# compare2_1.net
KiCad netlist of a schematic drawn in EAGLE
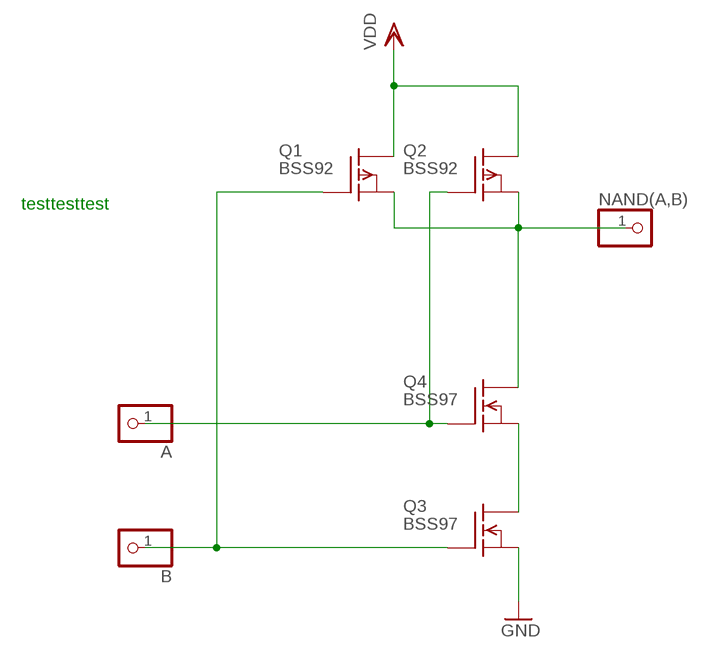
[diagram p0: schematic, sheet 1]

(export (version "E")
  (design (tool "Eeschema 10.0.6"))
  (components
    (comp (ref "A")
      (value "PINHD-1X1")
      (footprint "eagle-import:1X01")
      (libsource (lib "eagle-import") (part "PINHD-1X1"))
    )
    (comp (ref "B")
      (value "PINHD-1X1")
      (footprint "eagle-import:1X01")
      (libsource (lib "eagle-import") (part "PINHD-1X1"))
    )
    (comp (ref "NAND(A,B)")
      (value "PINHD-1X1")
      (footprint "eagle-import:1X01")
      (libsource (lib "eagle-import") (part "PINHD-1X1"))
    )
    (comp (ref "Q1")
      (value "BSS92")
      (footprint "eagle-import:TO92")
      (libsource (lib "eagle-import") (part "BSS92"))
    )
    (comp (ref "Q2")
      (value "BSS92")
      (footprint "eagle-import:TO92")
      (libsource (lib "eagle-import") (part "BSS92"))
    )
    (comp (ref "Q3")
      (value "BSS97")
      (footprint "eagle-import:TO202")
      (libsource (lib "eagle-import") (part "BSS97"))
    )
    (comp (ref "Q4")
      (value "BSS97")
      (footprint "eagle-import:TO202")
      (libsource (lib "eagle-import") (part "BSS97"))
    )
  )
  (nets
    (net (code "1") (name "GND") (class "Default")
      (node (ref "Q3") (pin "1") (pinfunction "S_1") (pintype "passive"))
    )
    (net (code "2") (name "Net-(Q1-G)") (class "Default")
      (node (ref "B") (pin "1") (pinfunction "1_1") (pintype "passive"))
      (node (ref "Q1") (pin "1") (pinfunction "G_1") (pintype "passive"))
      (node (ref "Q3") (pin "3") (pinfunction "G_3") (pintype "passive"))
    )
    (net (code "3") (name "Net-(Q1-S)") (class "Default")
      (node (ref "NAND(A,B)") (pin "1") (pinfunction "1_1") (pintype "passive"))
      (node (ref "Q1") (pin "3") (pinfunction "S_3") (pintype "passive"))
      (node (ref "Q2") (pin "3") (pinfunction "S_3") (pintype "passive"))
      (node (ref "Q4") (pin "2") (pinfunction "D_2") (pintype "passive"))
    )
    (net (code "4") (name "Net-(Q2-G)") (class "Default")
      (node (ref "A") (pin "1") (pinfunction "1_1") (pintype "passive"))
      (node (ref "Q2") (pin "1") (pinfunction "G_1") (pintype "passive"))
      (node (ref "Q4") (pin "3") (pinfunction "G_3") (pintype "passive"))
    )
    (net (code "5") (name "Net-(Q3-D)") (class "Default")
      (node (ref "Q3") (pin "2") (pinfunction "D_2") (pintype "passive"))
      (node (ref "Q4") (pin "1") (pinfunction "S_1") (pintype "passive"))
    )
    (net (code "6") (name "VDD") (class "Default")
      (node (ref "Q1") (pin "2") (pinfunction "D_2") (pintype "passive"))
      (node (ref "Q2") (pin "2") (pinfunction "D_2") (pintype "passive"))
    )
  )
)
